# Sheet1.net
KiCad netlist of a schematic drawn in Altium Designer
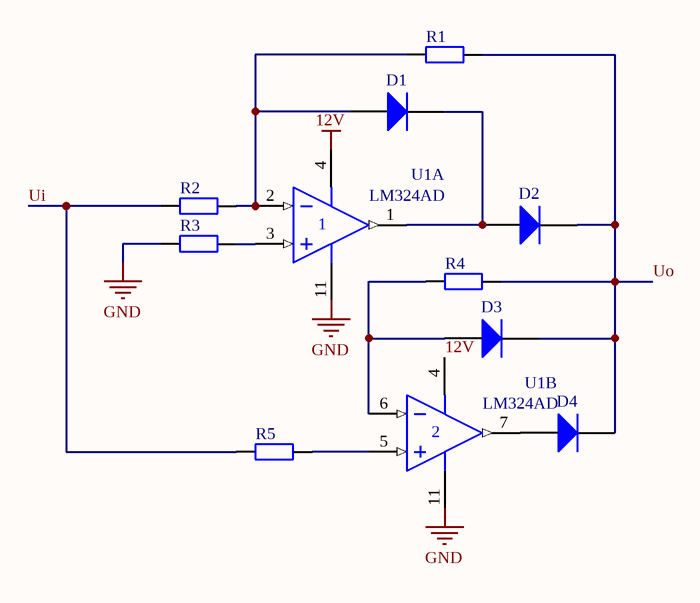
[diagram p0: Sheet1.SchDoc]

(export (version "E")
  (design (tool "Eeschema 10.0.6"))
  (components
    (comp (ref "D1")
      (value "Diode")
      (footprint "SMC")
      (description "Default Diode")
      (fields (field (name "PUBLISHER") "Altium Limited"))
      (libsource (lib "Miscellaneous Devices") (part "Diode"))
    )
    (comp (ref "D2")
      (value "Diode")
      (footprint "SMC")
      (description "Default Diode")
      (fields (field (name "PUBLISHER") "Altium Limited"))
      (libsource (lib "Miscellaneous Devices") (part "Diode"))
    )
    (comp (ref "D3")
      (value "Diode")
      (footprint "SMC")
      (description "Default Diode")
      (fields (field (name "PUBLISHER") "Altium Limited"))
      (libsource (lib "Miscellaneous Devices") (part "Diode"))
    )
    (comp (ref "D4")
      (value "Diode")
      (footprint "SMC")
      (description "Default Diode")
      (fields (field (name "PUBLISHER") "Altium Limited"))
      (libsource (lib "Miscellaneous Devices") (part "Diode"))
    )
    (comp (ref "R1")
      (value "Res2")
      (footprint "AXIAL-0.4")
      (description "Resistor")
      (fields (field (name "PUBLISHER") "Altium Limited"))
      (libsource (lib "Miscellaneous Devices") (part "Res2"))
    )
    (comp (ref "R2")
      (value "Res2")
      (footprint "AXIAL-0.4")
      (description "Resistor")
      (fields (field (name "PUBLISHER") "Altium Limited"))
      (libsource (lib "Miscellaneous Devices") (part "Res2"))
    )
    (comp (ref "R3")
      (value "Res2")
      (footprint "AXIAL-0.4")
      (description "Resistor")
      (fields (field (name "PUBLISHER") "Altium Limited"))
      (libsource (lib "Miscellaneous Devices") (part "Res2"))
    )
    (comp (ref "R4")
      (value "Res2")
      (footprint "AXIAL-0.4")
      (description "Resistor")
      (fields (field (name "PUBLISHER") "Altium Limited"))
      (libsource (lib "Miscellaneous Devices") (part "Res2"))
    )
    (comp (ref "R5")
      (value "Res2")
      (footprint "AXIAL-0.4")
      (description "Resistor")
      (fields (field (name "PUBLISHER") "Altium Limited"))
      (libsource (lib "Miscellaneous Devices") (part "Res2"))
    )
    (comp (ref "U1")
      (value "LM324AD")
      (footprint "SO-14")
      (description "Quadruple Operational Amplifier")
      (fields (field (name "PUBLISHER") "Altium Limited"))
      (libsource (lib "主板") (part "LM324AD"))
    )
  )
  (nets
    (net (code "1") (name "/Ui") (class "Default")
      (node (ref "R2") (pin "1") (pinfunction "1_1") (pintype "passive"))
      (node (ref "R5") (pin "1") (pinfunction "1_1") (pintype "passive"))
    )
    (net (code "2") (name "/Uo") (class "Default")
      (node (ref "D2") (pin "2") (pinfunction "K_2") (pintype "passive"))
      (node (ref "D3") (pin "2") (pinfunction "K_2") (pintype "passive"))
      (node (ref "D4") (pin "2") (pinfunction "K_2") (pintype "passive"))
      (node (ref "R1") (pin "2") (pinfunction "2_2") (pintype "passive"))
      (node (ref "R4") (pin "2") (pinfunction "2_2") (pintype "passive"))
    )
    (net (code "3") (name "12V") (class "Default")
      (node (ref "U1") (pin "4") (pinfunction "V+_4") (pintype "power_in"))
    )
    (net (code "4") (name "GND") (class "Default")
      (node (ref "R3") (pin "1") (pinfunction "1_1") (pintype "passive"))
      (node (ref "U1") (pin "11") (pinfunction "V-_11") (pintype "power_in"))
    )
    (net (code "5") (name "Net-(D1-A)") (class "Default")
      (node (ref "D1") (pin "1") (pinfunction "A_1") (pintype "passive"))
      (node (ref "R1") (pin "1") (pinfunction "1_1") (pintype "passive"))
      (node (ref "R2") (pin "2") (pinfunction "2_2") (pintype "passive"))
      (node (ref "U1") (pin "2") (pinfunction "IN-_2") (pintype "input"))
    )
    (net (code "6") (name "Net-(D1-K)") (class "Default")
      (node (ref "D1") (pin "2") (pinfunction "K_2") (pintype "passive"))
      (node (ref "D2") (pin "1") (pinfunction "A_1") (pintype "passive"))
      (node (ref "U1") (pin "1") (pinfunction "OUT_1") (pintype "output"))
    )
    (net (code "7") (name "Net-(D3-A)") (class "Default")
      (node (ref "D3") (pin "1") (pinfunction "A_1") (pintype "passive"))
      (node (ref "R4") (pin "1") (pinfunction "1_1") (pintype "passive"))
      (node (ref "U1") (pin "6") (pinfunction "IN-_6") (pintype "input"))
    )
    (net (code "8") (name "Net-(D4-A)") (class "Default")
      (node (ref "D4") (pin "1") (pinfunction "A_1") (pintype "passive"))
      (node (ref "U1") (pin "7") (pinfunction "OUT_7") (pintype "output"))
    )
    (net (code "9") (name "Net-(U1A-IN+)") (class "Default")
      (node (ref "R3") (pin "2") (pinfunction "2_2") (pintype "passive"))
      (node (ref "U1") (pin "3") (pinfunction "IN+_3") (pintype "input"))
    )
    (net (code "10") (name "Net-(U1B-IN+)") (class "Default")
      (node (ref "R5") (pin "2") (pinfunction "2_2") (pintype "passive"))
      (node (ref "U1") (pin "5") (pinfunction "IN+_5") (pintype "input"))
    )
  )
)
